# Master.net
KiCad netlist of a schematic drawn in Altium Designer
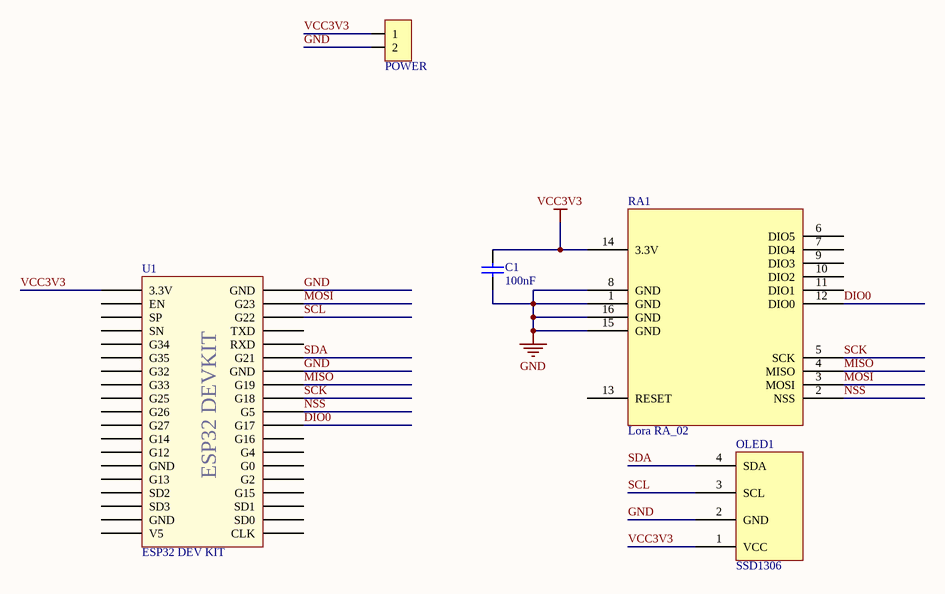
[diagram p0: Master.SchDoc]

(export (version "E")
  (design (tool "Eeschema 10.0.6"))
  (components
    (comp (ref "C1")
      (value "100nF")
      (footprint "tu 0603")
      (description "Dán")
      (libsource (lib "Altium_Lib_by_KhueNguyenCreator") (part "Tu 0603 104 50V 10%"))
    )
    (comp (ref "JP2")
      (value "POWER")
      (footprint "JP 1x2 CT")
      (description "Cắm")
      (libsource (lib "Altium_Lib_by_KhueNguyenCreator") (part "JP 1x2 2.54 Cai Thang"))
    )
    (comp (ref "OLED1") (value "SSD1306") (footprint "SSD1306") (libsource (lib "Schlib1") (part "SSD1306")))
    (comp (ref "RA1")
      (value "Lora RA_02")
      (footprint "SOP16")
      (libsource (lib "Schlib1") (part "Lora RA_02"))
    )
    (comp (ref "U1")
      (value "ESP32 DEV KIT")
      (footprint "ESP32 DEVKIT")
      (libsource (lib "Altium_Lib_by_KhueNguyenCreator") (part "ESP32 DEV KIT"))
    )
  )
  (nets
    (net (code "1") (name "/DIO0") (class "Default")
      (node (ref "RA1") (pin "12") (pinfunction "DIO0_12") (pintype "passive"))
      (node (ref "U1") (pin "28") (pinfunction "G17_28") (pintype "passive"))
    )
    (net (code "2") (name "/MISO") (class "Default")
      (node (ref "RA1") (pin "4") (pinfunction "MISO_4") (pintype "passive"))
      (node (ref "U1") (pin "31") (pinfunction "G19_31") (pintype "passive"))
    )
    (net (code "3") (name "/MOSI") (class "Default")
      (node (ref "RA1") (pin "3") (pinfunction "MOSI_3") (pintype "passive"))
      (node (ref "U1") (pin "37") (pinfunction "G23_37") (pintype "passive"))
    )
    (net (code "4") (name "/NSS") (class "Default")
      (node (ref "RA1") (pin "2") (pinfunction "NSS_2") (pintype "passive"))
      (node (ref "U1") (pin "29") (pinfunction "G5_29") (pintype "passive"))
    )
    (net (code "5") (name "/SCK") (class "Default")
      (node (ref "RA1") (pin "5") (pinfunction "SCK_5") (pintype "passive"))
      (node (ref "U1") (pin "30") (pinfunction "G18_30") (pintype "passive"))
    )
    (net (code "6") (name "/SCL") (class "Default")
      (node (ref "OLED1") (pin "3") (pinfunction "SCL_3") (pintype "passive"))
      (node (ref "U1") (pin "36") (pinfunction "G22_36") (pintype "passive"))
    )
    (net (code "7") (name "/SDA") (class "Default")
      (node (ref "OLED1") (pin "4") (pinfunction "SDA_4") (pintype "passive"))
      (node (ref "U1") (pin "33") (pinfunction "G21_33") (pintype "passive"))
    )
    (net (code "8") (name "GND") (class "Default")
      (node (ref "C1") (pin "2") (pinfunction "2_2") (pintype "passive"))
      (node (ref "JP2") (pin "2") (pinfunction "2_2") (pintype "passive"))
      (node (ref "OLED1") (pin "2") (pinfunction "GND_2") (pintype "passive"))
      (node (ref "RA1") (pin "1") (pinfunction "GND_1") (pintype "passive"))
      (node (ref "RA1") (pin "15") (pinfunction "GND_15") (pintype "passive"))
      (node (ref "RA1") (pin "16") (pinfunction "GND_16") (pintype "passive"))
      (node (ref "RA1") (pin "8") (pinfunction "GND_8") (pintype "passive"))
      (node (ref "U1") (pin "32") (pinfunction "GND_32") (pintype "passive"))
      (node (ref "U1") (pin "38") (pinfunction "GND_38") (pintype "passive"))
    )
    (net (code "9") (name "VCC3V3") (class "Default")
      (node (ref "C1") (pin "1") (pinfunction "1_1") (pintype "passive"))
      (node (ref "JP2") (pin "1") (pinfunction "1_1") (pintype "passive"))
      (node (ref "OLED1") (pin "1") (pinfunction "VCC_1") (pintype "passive"))
      (node (ref "RA1") (pin "14") (pinfunction "3.3V_14") (pintype "passive"))
      (node (ref "U1") (pin "1") (pinfunction "3.3V_1") (pintype "passive"))
    )
    (net (code "10") (name "unconnected-(RA1-DIO1-Pad11)") (class "Default")
      (node (ref "RA1") (pin "11") (pinfunction "DIO1_11") (pintype "passive"))
    )
    (net (code "11") (name "unconnected-(RA1-DIO2-Pad10)") (class "Default")
      (node (ref "RA1") (pin "10") (pinfunction "DIO2_10") (pintype "passive"))
    )
    (net (code "12") (name "unconnected-(RA1-DIO3-Pad9)") (class "Default")
      (node (ref "RA1") (pin "9") (pinfunction "DIO3_9") (pintype "passive"))
    )
    (net (code "13") (name "unconnected-(RA1-DIO4-Pad7)") (class "Default")
      (node (ref "RA1") (pin "7") (pinfunction "DIO4_7") (pintype "passive"))
    )
    (net (code "14") (name "unconnected-(RA1-DIO5-Pad6)") (class "Default")
      (node (ref "RA1") (pin "6") (pinfunction "DIO5_6") (pintype "passive"))
    )
    (net (code "15") (name "unconnected-(RA1-RESET-Pad13)") (class "Default")
      (node (ref "RA1") (pin "13") (pinfunction "RESET_13") (pintype "passive"))
    )
    (net (code "16") (name "unconnected-(U1-CLK-Pad20)") (class "Default")
      (node (ref "U1") (pin "20") (pinfunction "CLK_20") (pintype "passive"))
    )
    (net (code "17") (name "unconnected-(U1-EN-Pad2)") (class "Default")
      (node (ref "U1") (pin "2") (pinfunction "EN_2") (pintype "passive"))
    )
    (net (code "18") (name "unconnected-(U1-G0-Pad25)") (class "Default")
      (node (ref "U1") (pin "25") (pinfunction "G0_25") (pintype "passive"))
    )
    (net (code "19") (name "unconnected-(U1-G2-Pad24)") (class "Default")
      (node (ref "U1") (pin "24") (pinfunction "G2_24") (pintype "passive"))
    )
    (net (code "20") (name "unconnected-(U1-G4-Pad26)") (class "Default")
      (node (ref "U1") (pin "26") (pinfunction "G4_26") (pintype "passive"))
    )
    (net (code "21") (name "unconnected-(U1-G12-Pad13)") (class "Default")
      (node (ref "U1") (pin "13") (pinfunction "G12_13") (pintype "passive"))
    )
    (net (code "22") (name "unconnected-(U1-G13-Pad15)") (class "Default")
      (node (ref "U1") (pin "15") (pinfunction "G13_15") (pintype "passive"))
    )
    (net (code "23") (name "unconnected-(U1-G14-Pad12)") (class "Default")
      (node (ref "U1") (pin "12") (pinfunction "G14_12") (pintype "passive"))
    )
    (net (code "24") (name "unconnected-(U1-G15-Pad23)") (class "Default")
      (node (ref "U1") (pin "23") (pinfunction "G15_23") (pintype "passive"))
    )
    (net (code "25") (name "unconnected-(U1-G16-Pad27)") (class "Default")
      (node (ref "U1") (pin "27") (pinfunction "G16_27") (pintype "passive"))
    )
    (net (code "26") (name "unconnected-(U1-G25-Pad9)") (class "Default")
      (node (ref "U1") (pin "9") (pinfunction "G25_9") (pintype "passive"))
    )
    (net (code "27") (name "unconnected-(U1-G26-Pad10)") (class "Default")
      (node (ref "U1") (pin "10") (pinfunction "G26_10") (pintype "passive"))
    )
    (net (code "28") (name "unconnected-(U1-G27-Pad11)") (class "Default")
      (node (ref "U1") (pin "11") (pinfunction "G27_11") (pintype "passive"))
    )
    (net (code "29") (name "unconnected-(U1-G32-Pad7)") (class "Default")
      (node (ref "U1") (pin "7") (pinfunction "G32_7") (pintype "passive"))
    )
    (net (code "30") (name "unconnected-(U1-G33-Pad8)") (class "Default")
      (node (ref "U1") (pin "8") (pinfunction "G33_8") (pintype "passive"))
    )
    (net (code "31") (name "unconnected-(U1-G34-Pad5)") (class "Default")
      (node (ref "U1") (pin "5") (pinfunction "G34_5") (pintype "passive"))
    )
    (net (code "32") (name "unconnected-(U1-G35-Pad6)") (class "Default")
      (node (ref "U1") (pin "6") (pinfunction "G35_6") (pintype "passive"))
    )
    (net (code "33") (name "unconnected-(U1-GND-Pad14)") (class "Default")
      (node (ref "U1") (pin "14") (pinfunction "GND_14") (pintype "passive"))
    )
    (net (code "34") (name "unconnected-(U1-GND-Pad18)") (class "Default")
      (node (ref "U1") (pin "18") (pinfunction "GND_18") (pintype "passive"))
    )
    (net (code "35") (name "unconnected-(U1-RXD-Pad34)") (class "Default")
      (node (ref "U1") (pin "34") (pinfunction "RXD_34") (pintype "passive"))
    )
    (net (code "36") (name "unconnected-(U1-SD0-Pad21)") (class "Default")
      (node (ref "U1") (pin "21") (pinfunction "SD0_21") (pintype "passive"))
    )
    (net (code "37") (name "unconnected-(U1-SD1-Pad22)") (class "Default")
      (node (ref "U1") (pin "22") (pinfunction "SD1_22") (pintype "passive"))
    )
    (net (code "38") (name "unconnected-(U1-SD2-Pad16)") (class "Default")
      (node (ref "U1") (pin "16") (pinfunction "SD2_16") (pintype "passive"))
    )
    (net (code "39") (name "unconnected-(U1-SD3-Pad17)") (class "Default")
      (node (ref "U1") (pin "17") (pinfunction "SD3_17") (pintype "passive"))
    )
    (net (code "40") (name "unconnected-(U1-SN-Pad4)") (class "Default")
      (node (ref "U1") (pin "4") (pinfunction "SN_4") (pintype "passive"))
    )
    (net (code "41") (name "unconnected-(U1-SP-Pad3)") (class "Default")
      (node (ref "U1") (pin "3") (pinfunction "SP_3") (pintype "passive"))
    )
    (net (code "42") (name "unconnected-(U1-TXD-Pad35)") (class "Default")
      (node (ref "U1") (pin "35") (pinfunction "TXD_35") (pintype "passive"))
    )
    (net (code "43") (name "unconnected-(U1-V5-Pad19)") (class "Default")
      (node (ref "U1") (pin "19") (pinfunction "V5_19") (pintype "passive"))
    )
  )
)
